# untitled2.net
KiCad netlist of a schematic drawn in EAGLE
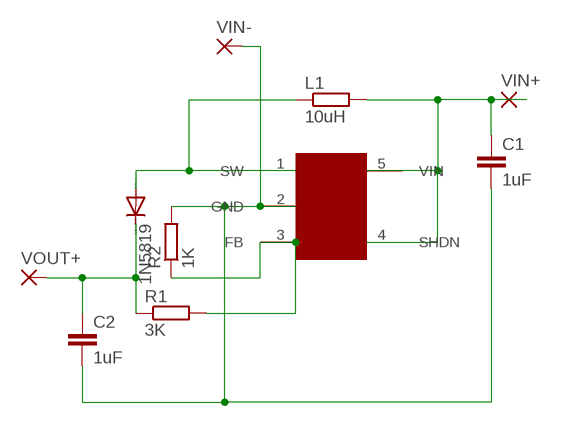
[diagram p0: schematic, sheet 1]

(export (version "E")
  (design (tool "Eeschema 10.0.6"))
  (components
    (comp (ref "1N5819")
      (value "DIODE-DO214AC")
      (footprint "eagle-import:DO214AC")
      (libsource (lib "eagle-import") (part "DIODE-DO214AC"))
    )
    (comp (ref "C1")
      (value "1uF")
      (footprint "eagle-import:C1206")
      (libsource (lib "eagle-import") (part "C-EUC1206"))
    )
    (comp (ref "C2")
      (value "1uF")
      (footprint "eagle-import:C1206")
      (libsource (lib "eagle-import") (part "C-EUC1206"))
    )
    (comp (ref "L1")
      (value "10uH")
      (footprint "eagle-import:R0805")
      (libsource (lib "eagle-import") (part "R-EU_R0805"))
    )
    (comp (ref "R1")
      (value "3K")
      (footprint "eagle-import:R1206")
      (libsource (lib "eagle-import") (part "R-EU_R1206"))
    )
    (comp (ref "R2")
      (value "1K")
      (footprint "eagle-import:R1206")
      (libsource (lib "eagle-import") (part "R-EU_R1206"))
    )
    (comp (ref "U$8")
      (value "AP3012")
      (footprint "eagle-import:SOT-23-5")
      (libsource (lib "eagle-import") (part "AP3012"))
    )
    (comp (ref "VIN+")
      (value "SMD2")
      (footprint "eagle-import:SMD1,27-2,54")
      (libsource (lib "eagle-import") (part "SMD2"))
    )
    (comp (ref "VIN-")
      (value "SMD2")
      (footprint "eagle-import:SMD1,27-2,54")
      (libsource (lib "eagle-import") (part "SMD2"))
    )
    (comp (ref "VOUT+")
      (value "SMD2")
      (footprint "eagle-import:SMD1,27-2,54")
      (libsource (lib "eagle-import") (part "SMD2"))
    )
  )
  (nets
    (net (code "1") (name "Net-(U$8-FB)") (class "Default")
      (node (ref "R1") (pin "2") (pinfunction "2_2") (pintype "passive"))
      (node (ref "R2") (pin "1") (pinfunction "1_1") (pintype "passive"))
      (node (ref "U$8") (pin "3") (pinfunction "FB_3") (pintype "bidirectional"))
    )
    (net (code "2") (name "Net-(U$8-GND)") (class "Default")
      (node (ref "C1") (pin "2") (pinfunction "2_2") (pintype "passive"))
      (node (ref "C2") (pin "2") (pinfunction "2_2") (pintype "passive"))
      (node (ref "R2") (pin "2") (pinfunction "2_2") (pintype "passive"))
      (node (ref "U$8") (pin "2") (pinfunction "GND_2") (pintype "bidirectional"))
      (node (ref "VIN-") (pin "1") (pinfunction "P_1") (pintype "passive"))
    )
    (net (code "3") (name "Net-(U$8-SHDN)") (class "Default")
      (node (ref "C1") (pin "1") (pinfunction "1_1") (pintype "passive"))
      (node (ref "L1") (pin "2") (pinfunction "2_2") (pintype "passive"))
      (node (ref "U$8") (pin "4") (pinfunction "SHDN_4") (pintype "bidirectional"))
      (node (ref "U$8") (pin "5") (pinfunction "VIN_5") (pintype "bidirectional"))
      (node (ref "VIN+") (pin "1") (pinfunction "P_1") (pintype "passive"))
    )
    (net (code "4") (name "Net-(U$8-SW)") (class "Default")
      (node (ref "1N5819") (pin "A") (pinfunction "A_A") (pintype "passive"))
      (node (ref "L1") (pin "1") (pinfunction "1_1") (pintype "passive"))
      (node (ref "U$8") (pin "1") (pinfunction "SW_1") (pintype "bidirectional"))
    )
    (net (code "5") (name "Net-(VOUT+-P)") (class "Default")
      (node (ref "1N5819") (pin "C") (pinfunction "C_C") (pintype "passive"))
      (node (ref "C2") (pin "1") (pinfunction "1_1") (pintype "passive"))
      (node (ref "R1") (pin "1") (pinfunction "1_1") (pintype "passive"))
      (node (ref "VOUT+") (pin "1") (pinfunction "P_1") (pintype "passive"))
    )
  )
)
